# Transcurrent.net
KiCad netlist of a schematic drawn in Altium Designer
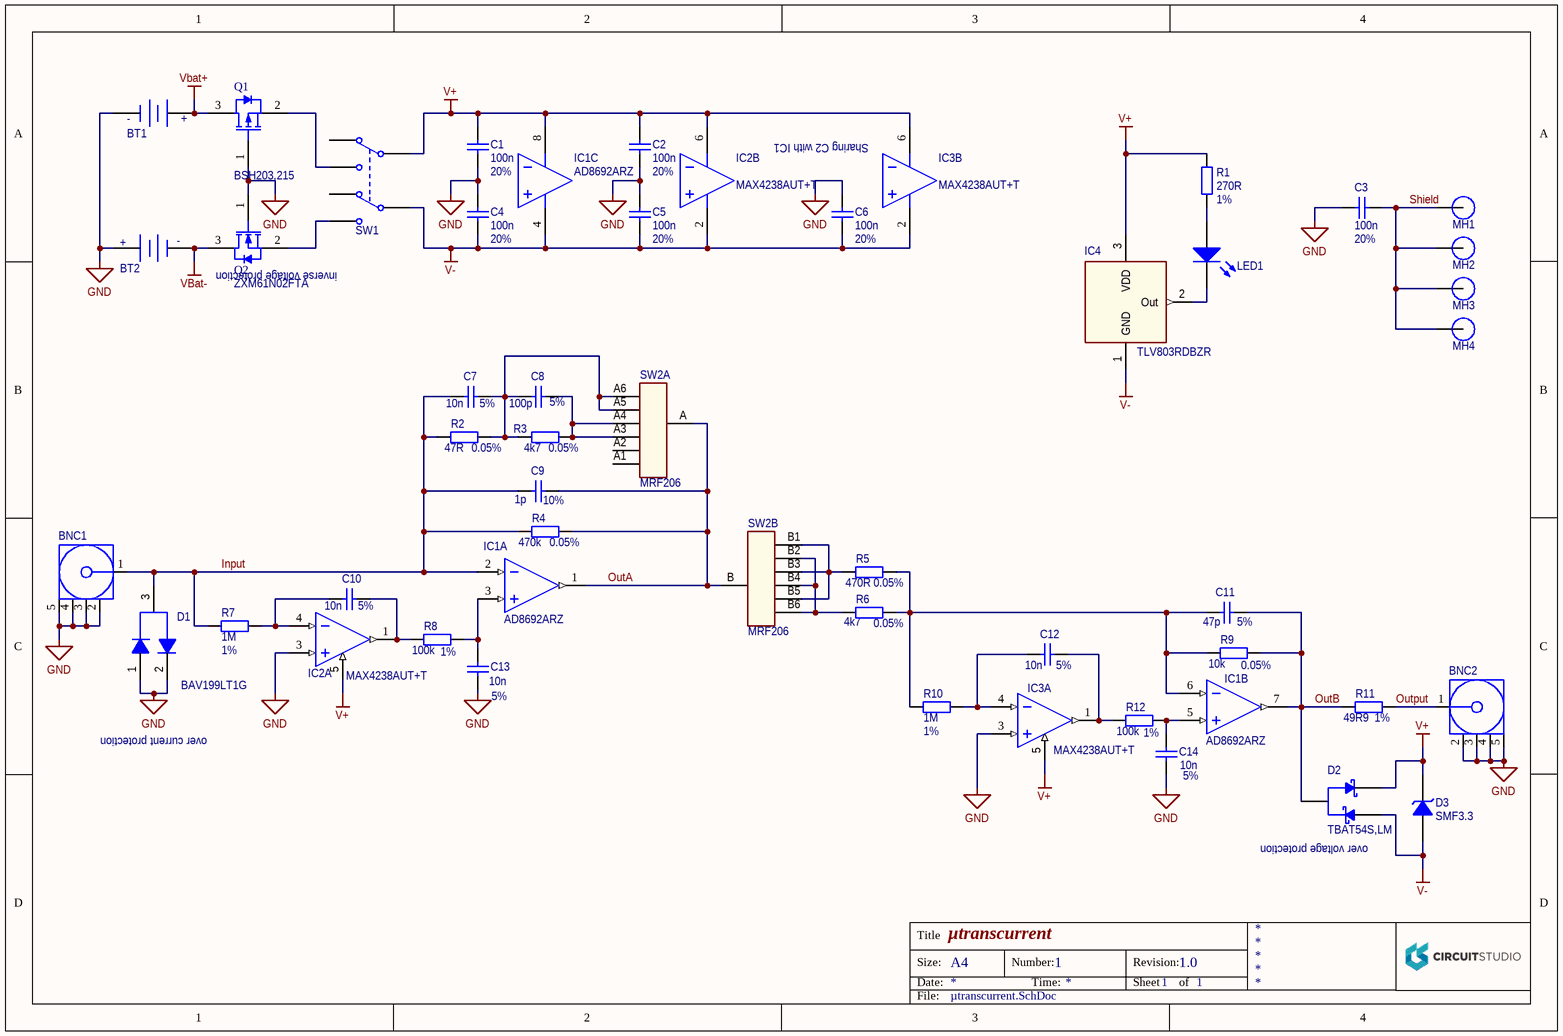
[diagram p0: Transcurrent.SchDoc]

(export (version "E")
  (design (tool "Eeschema 10.0.6"))
  (components
    (comp (ref "BNC1")
      (value "BNC female angled")
      (footprint "BNC 90°")
      (description "Connector, BNC THT 50R angled")
      (fields (field (name "MPN") "J01001A1948") (field (name "MANUFACTURER") "Telegärtner"))
      (libsource (lib "Transcurrent") (part "J01001A1948"))
    )
    (comp (ref "BNC2")
      (value "BNC female angled")
      (footprint "BNC 90°")
      (description "Connector, BNC THT 50R angled")
      (fields (field (name "MPN") "J01001A1948") (field (name "MANUFACTURER") "Telegärtner"))
      (libsource (lib "Transcurrent") (part "J01001A1948"))
    )
    (comp (ref "BT1")
      (value "Battery")
      (footprint "Keystone1020")
      (description "BATTERY HOLDER AAA SMD TAB")
      (fields (field (name "MANUFACTURER") "Keystone Electronics") (field (name "MPN") "1020"))
      (libsource (lib "Transcurrent") (part "Keystone1020"))
    )
    (comp (ref "BT2")
      (value "Battery")
      (footprint "Keystone1020")
      (description "BATTERY HOLDER AAA SMD TAB")
      (fields (field (name "MANUFACTURER") "Keystone Electronics") (field (name "MPN") "1020"))
      (libsource (lib "Transcurrent") (part "Keystone1020"))
    )
    (comp (ref "C1")
      (value "100n")
      (footprint "C0805")
      (description "Capacitor 100n 20% 0805")
      (fields
        (field (name "MANUFACTURER") "Any")
        (field (name "TOLERANCE") "20%")
        (field (name "Comment") "Cap 100n 0805")
      )
      (libsource (lib "RCL") (part "C0805_100n"))
    )
    (comp (ref "C2")
      (value "100n")
      (footprint "C0805")
      (description "Capacitor 100n 20% 0805")
      (fields
        (field (name "MANUFACTURER") "Any")
        (field (name "TOLERANCE") "20%")
        (field (name "Comment") "Cap 100n 0805")
      )
      (libsource (lib "RCL") (part "C0805_100n"))
    )
    (comp (ref "C3")
      (value "100n")
      (footprint "C0805")
      (description "Capacitor 100n 20% 0805")
      (fields
        (field (name "MANUFACTURER") "Any")
        (field (name "TOLERANCE") "20%")
        (field (name "Comment") "Cap 100n 0805")
      )
      (libsource (lib "RCL") (part "C0805_100n"))
    )
    (comp (ref "C4")
      (value "100n")
      (footprint "C0805")
      (description "Capacitor 100n 20% 0805")
      (fields
        (field (name "MANUFACTURER") "Any")
        (field (name "TOLERANCE") "20%")
        (field (name "Comment") "Cap 100n 0805")
      )
      (libsource (lib "RCL") (part "C0805_100n"))
    )
    (comp (ref "C5")
      (value "100n")
      (footprint "C0805")
      (description "Capacitor 100n 20% 0805")
      (fields
        (field (name "MANUFACTURER") "Any")
        (field (name "TOLERANCE") "20%")
        (field (name "Comment") "Cap 100n 0805")
      )
      (libsource (lib "RCL") (part "C0805_100n"))
    )
    (comp (ref "C6")
      (value "100n")
      (footprint "C0805")
      (description "Capacitor 100n 20% 0805")
      (fields
        (field (name "MANUFACTURER") "Any")
        (field (name "TOLERANCE") "20%")
        (field (name "Comment") "Cap 100n 0805")
      )
      (libsource (lib "RCL") (part "C0805_100n"))
    )
    (comp (ref "C7")
      (value "10n")
      (footprint "C0805")
      (description "CAP CER 10nF 50V C0G/NP0 0805")
      (fields
        (field (name "MPN") "C0805C103J5GACTU")
        (field (name "MANUFACTURER") "Kemet")
        (field (name "TOLERANCE") "5%")
      )
      (libsource (lib "Transcurrent") (part "C0805C103J5GACTU"))
    )
    (comp (ref "C8")
      (value "100p")
      (footprint "C0805")
      (description "CAP CER 100PF 100V C0G/NP0 0805")
      (fields
        (field (name "MPN") "CL21C101JC61PNC")
        (field (name "MANUFACTURER") "Samsung")
        (field (name "TOLERANCE") "5%")
      )
      (libsource (lib "Transcurrent") (part "CL21C101JC61PNC"))
    )
    (comp (ref "C9")
      (value "1p")
      (footprint "C0805")
      (description "CAP CER 1PF 50V NPO 0805")
      (fields
        (field (name "MPN") "CC0805BRNPO9BN1R0")
        (field (name "MANUFACTURER") "Yageo")
        (field (name "TOLERANCE") "10%")
      )
      (libsource (lib "Transcurrent") (part "CC0805BRNPO9BN1R0"))
    )
    (comp (ref "C10")
      (value "10n")
      (footprint "C0805")
      (description "CAP CER 10nF 50V C0G/NP0 0805")
      (fields
        (field (name "MPN") "C0805C103J5GACTU")
        (field (name "MANUFACTURER") "Kemet")
        (field (name "TOLERANCE") "5%")
      )
      (libsource (lib "Transcurrent") (part "C0805C103J5GACTU"))
    )
    (comp (ref "C11")
      (value "47p")
      (footprint "C0805")
      (description "CAP CER 47PF 50V C0G/NPO 0805")
      (fields
        (field (name "MPN") "CC0805JRNPO9BN470")
        (field (name "MANUFACTURER") "Yageo")
        (field (name "TOLERANCE") "5%")
      )
      (libsource (lib "Transcurrent") (part "CC0805JRNPO9BN470"))
    )
    (comp (ref "C12")
      (value "10n")
      (footprint "C0805")
      (description "CAP CER 10nF 50V C0G/NP0 0805")
      (fields
        (field (name "MPN") "C0805C103J5GACTU")
        (field (name "MANUFACTURER") "Kemet")
        (field (name "TOLERANCE") "5%")
      )
      (libsource (lib "Transcurrent") (part "C0805C103J5GACTU"))
    )
    (comp (ref "C13")
      (value "10n")
      (footprint "C0805")
      (description "CAP CER 10nF 50V C0G/NP0 0805")
      (fields
        (field (name "MPN") "C0805C103J5GACTU")
        (field (name "MANUFACTURER") "Kemet")
        (field (name "TOLERANCE") "5%")
      )
      (libsource (lib "Transcurrent") (part "C0805C103J5GACTU"))
    )
    (comp (ref "C14")
      (value "10n")
      (footprint "C0805")
      (description "CAP CER 10nF 50V C0G/NP0 0805")
      (fields
        (field (name "MPN") "C0805C103J5GACTU")
        (field (name "MANUFACTURER") "Kemet")
        (field (name "TOLERANCE") "5%")
      )
      (libsource (lib "Transcurrent") (part "C0805C103J5GACTU"))
    )
    (comp (ref "D1")
      (value "BAV199LT1G")
      (footprint "SOT23-3")
      (description "DIODE ARRAY GP 70V 215MA SOT23-3")
      (fields (field (name "MANUFACTURER") "ON Semiconductor") (field (name "MPN") "BAV199LT1G"))
      (libsource (lib "Transcurrent") (part "BAV199LT1G"))
    )
    (comp (ref "D2")
      (value "TBAT54S")
      (footprint "SOT23-3")
      (description "DIODE SCHOTTKY 30V 140MA SOT23")
      (fields (field (name "MANUFACTURER") "Toshiba") (field (name "MPN") "TBAT54S,LM"))
      (libsource (lib "Transcurrent") (part "TBAT54S"))
    )
    (comp (ref "D3")
      (value "D Zener")
      (footprint "SOD 123-FL")
      (description "TVS DIODE 3.3V 6.8V SOD123FL")
      (fields (field (name "MANUFACTURER") "Littelfuse Inc.") (field (name "MPN") "SMF3.3"))
      (libsource (lib "Transcurrent") (part "SMF3.3"))
    )
    (comp (ref "IC1")
      (value "AD8692ARZ")
      (footprint "SO8_N")
      (description "IC OPAMP GP 10MHZ RRO 8SOIC")
      (fields (field (name "MANUFACTURER") "Analog Devices") (field (name "MPN") "AD8692ARZ"))
      (libsource (lib "Transcurrent") (part "AD8692ARZ"))
    )
    (comp (ref "IC2")
      (value "MAX4238AUT+T")
      (footprint "SOT23-6")
      (description "OpAmp, low noise, auto zero")
      (fields (field (name "MANUFACTURER") "Maxim Integrated") (field (name "MPN") "MAX4238AUT+T"))
      (libsource (lib "Transcurrent") (part "MAX4238AUT+T"))
    )
    (comp (ref "IC3")
      (value "MAX4238AUT+T")
      (footprint "SOT23-6")
      (description "OpAmp, low noise, auto zero")
      (fields (field (name "MANUFACTURER") "Maxim Integrated") (field (name "MPN") "MAX4238AUT+T"))
      (libsource (lib "Transcurrent") (part "MAX4238AUT+T"))
    )
    (comp (ref "IC4")
      (value "TLV803RDBZR")
      (footprint "SOT23-3")
      (description "IC VOLT SUPERVISOR 2.64V SOT23-3")
      (fields (field (name "MANUFACTURER") "Texas Instruments") (field (name "MPN") "TLV803RDBZR"))
      (libsource (lib "Transcurrent") (part "TLV803RDBZR"))
    )
    (comp (ref "LED1")
      (value "LED")
      (footprint "LED_1206_revers")
      (description "LED rot 1206 revers")
      (fields (field (name "MPN") "156120RS75300") (field (name "MANUFACTURER") "Würth Elektronik"))
      (libsource (lib "Transcurrent") (part "156120RS75300"))
    )
    (comp (ref "MH1")
      (value "Mounting Hole M3.5")
      (footprint "M3.5 DIN84")
      (libsource (lib "Transcurrent") (part "Mounting Hole M3.5"))
    )
    (comp (ref "MH2")
      (value "Mounting Hole M3.5")
      (footprint "M3.5 DIN84")
      (libsource (lib "Transcurrent") (part "Mounting Hole M3.5"))
    )
    (comp (ref "MH3")
      (value "Mounting Hole M3.5")
      (footprint "M3.5 DIN84")
      (libsource (lib "Transcurrent") (part "Mounting Hole M3.5"))
    )
    (comp (ref "MH4")
      (value "Mounting Hole M3.5")
      (footprint "M3.5 DIN84")
      (libsource (lib "Transcurrent") (part "Mounting Hole M3.5"))
    )
    (comp (ref "Q1")
      (value "BSH203,215")
      (footprint "SOT23-3")
      (description "MOSFET P-CH 30V 470MA SOT23")
      (fields (field (name "MANUFACTURER") "Nexperia") (field (name "MPN") "BSH203,215"))
      (libsource (lib "Transcurrent") (part "BSH203,215"))
    )
    (comp (ref "Q2")
      (value "ZXM61N02FTA")
      (footprint "SOT23-3")
      (description "MOSFET N-CH 20V 1.7A SOT23-3")
      (fields (field (name "MANUFACTURER") "Diodes Inc.") (field (name "MPN") "ZXM61N02FTA"))
      (libsource (lib "Transcurrent") (part "ZXM61N02FTA"))
    )
    (comp (ref "R1")
      (value "270R")
      (footprint "R0805")
      (description "Resistor 270R 1% 0805")
      (fields
        (field (name "MANUFACTURER") "Any")
        (field (name "TOLERANCE") "1%")
        (field (name "Comment") "Res 270R 0805")
      )
      (libsource (lib "RCL") (part "R0805_270R"))
    )
    (comp (ref "R2")
      (value "47R")
      (footprint "R0805")
      (description "RES SMD 47 OHM 0.05% 1/8W 0805")
      (fields
        (field (name "MPN") "RG2012N-470-W-T1")
        (field (name "MANUFACTURER") "Susumu")
        (field (name "TOLERANCE") "0.05%")
      )
      (libsource (lib "Transcurrent") (part "RG2012N-470-W-T1"))
    )
    (comp (ref "R3")
      (value "4k7")
      (footprint "R0805")
      (description "RES SMD 4k7 OHM 0.05% 1/8W 0805")
      (fields
        (field (name "MPN") "ERA-6ARW472V")
        (field (name "MANUFACTURER") "Panasonic")
        (field (name "TOLERANCE") "0.05%")
      )
      (libsource (lib "Transcurrent") (part "ERA-6ARW472V"))
    )
    (comp (ref "R4")
      (value "470k")
      (footprint "R0805")
      (description "RES SMD 470K OHM 0.05% 1/8W 0805")
      (fields
        (field (name "MPN") "RG2012N-474-W-T1")
        (field (name "MANUFACTURER") "Susumu")
        (field (name "TOLERANCE") "0.05%")
      )
      (libsource (lib "Transcurrent") (part "RG2012N-474-W-T1"))
    )
    (comp (ref "R5")
      (value "470R")
      (footprint "R0805")
      (description "RES SMD 470 OHM 0.05% 1/8W 0805")
      (fields
        (field (name "MPN") "RG2012N-471-W-T1")
        (field (name "MANUFACTURER") "Susumu")
        (field (name "TOLERANCE") "0.05%")
      )
      (libsource (lib "Transcurrent") (part "RG2012N-471-W-T1"))
    )
    (comp (ref "R6")
      (value "4k7")
      (footprint "R0805")
      (description "RES SMD 4k7 OHM 0.05% 1/8W 0805")
      (fields
        (field (name "MPN") "ERA-6ARW472V")
        (field (name "MANUFACTURER") "Panasonic")
        (field (name "TOLERANCE") "0.05%")
      )
      (libsource (lib "Transcurrent") (part "ERA-6ARW472V"))
    )
    (comp (ref "R7")
      (value "1M")
      (footprint "R0805")
      (description "Resistor 1M 1% 0805")
      (fields
        (field (name "TOLERANCE") "1%")
        (field (name "MANUFACTURER") "Any")
        (field (name "Comment") "Res 1M 0805")
      )
      (libsource (lib "RCL") (part "R0805_1M"))
    )
    (comp (ref "R8")
      (value "100k")
      (footprint "R0805")
      (description "Resistor 100k 1% 0805")
      (fields
        (field (name "TOLERANCE") "1%")
        (field (name "MANUFACTURER") "Any")
        (field (name "Comment") "Res 100k 0805")
      )
      (libsource (lib "RCL") (part "R0805_100k"))
    )
    (comp (ref "R9")
      (value "10k")
      (footprint "R0805")
      (description "RES SMD 10K OHM 0.05% 1/8W 0805")
      (fields
        (field (name "MPN") "RG2012N-103-W-T1")
        (field (name "MANUFACTURER") "Susumu")
        (field (name "TOLERANCE") "0.05%")
      )
      (libsource (lib "Transcurrent") (part "RG2012N-103-W-T1"))
    )
    (comp (ref "R10")
      (value "1M")
      (footprint "R0805")
      (description "Resistor 1M 1% 0805")
      (fields
        (field (name "TOLERANCE") "1%")
        (field (name "MANUFACTURER") "Any")
        (field (name "Comment") "Res 1M 0805")
      )
      (libsource (lib "RCL") (part "R0805_1M"))
    )
    (comp (ref "R11")
      (value "49R9")
      (footprint "R0805")
      (description "Resistor 49R9 1% 0805")
      (fields
        (field (name "MANUFACTURER") "Any")
        (field (name "TOLERANCE") "1%")
        (field (name "Comment") "Res 49R9 0805")
      )
      (libsource (lib "MyLibrary") (part "R0805_49R9"))
    )
    (comp (ref "R12")
      (value "100k")
      (footprint "R0805")
      (description "Resistor 100k 1% 0805")
      (fields
        (field (name "TOLERANCE") "1%")
        (field (name "MANUFACTURER") "Any")
        (field (name "Comment") "Res 100k 0805")
      )
      (libsource (lib "RCL") (part "R0805_100k"))
    )
    (comp (ref "SW1")
      (value "MMP 221")
      (footprint "MMP 221")
      (description "Switch, DPDT THT mini")
      (fields (field (name "MANUFACTURER") "Knitterswitch") (field (name "MPN") "221"))
      (libsource (lib "Transcurrent") (part "MMP 221"))
    )
    (comp (ref "SW2")
      (value "MRF206")
      (footprint "MKF206")
      (description "DP6T Rotary Switch")
      (fields (field (name "MANUFACTURER") "NKK Switches"))
      (libsource (lib "") (part "MRF206_1"))
    )
  )
  (nets
    (net (code "1") (name "/Input") (class "Default")
      (node (ref "BNC1") (pin "1") (pinfunction "Signal_1") (pintype "passive"))
      (node (ref "C7") (pin "1") (pinfunction "1_1") (pintype "passive"))
      (node (ref "C9") (pin "1") (pinfunction "1_1") (pintype "passive"))
      (node (ref "D1") (pin "3") (pinfunction "3_3") (pintype "passive"))
      (node (ref "IC1") (pin "2") (pinfunction "INA-_2") (pintype "input"))
      (node (ref "R2") (pin "1") (pinfunction "1_1") (pintype "passive"))
      (node (ref "R4") (pin "1") (pinfunction "1_1") (pintype "passive"))
      (node (ref "R7") (pin "1") (pinfunction "1_1") (pintype "passive"))
    )
    (net (code "2") (name "/OutA") (class "Default")
      (node (ref "C9") (pin "2") (pinfunction "2_2") (pintype "passive"))
      (node (ref "IC1") (pin "1") (pinfunction "OUTA_1") (pintype "output"))
      (node (ref "R4") (pin "2") (pinfunction "2_2") (pintype "passive"))
      (node (ref "SW2") (pin "A") (pinfunction "A_A") (pintype "passive"))
      (node (ref "SW2") (pin "B") (pinfunction "B_B") (pintype "passive"))
    )
    (net (code "3") (name "/OutB") (class "Default")
      (node (ref "C11") (pin "2") (pinfunction "2_2") (pintype "passive"))
      (node (ref "D2") (pin "3") (pinfunction "3_3") (pintype "passive"))
      (node (ref "IC1") (pin "7") (pinfunction "OUTB_7") (pintype "output"))
      (node (ref "R11") (pin "1") (pinfunction "1_1") (pintype "passive"))
      (node (ref "R9") (pin "2") (pinfunction "2_2") (pintype "passive"))
    )
    (net (code "4") (name "/Output") (class "Default")
      (node (ref "BNC2") (pin "1") (pinfunction "Signal_1") (pintype "passive"))
      (node (ref "R11") (pin "2") (pinfunction "2_2") (pintype "passive"))
    )
    (net (code "5") (name "/Shield") (class "Default")
      (node (ref "C3") (pin "2") (pinfunction "2_2") (pintype "passive"))
      (node (ref "MH1") (pin "0") (pinfunction "0_0") (pintype "passive"))
      (node (ref "MH2") (pin "0") (pinfunction "0_0") (pintype "passive"))
      (node (ref "MH3") (pin "0") (pinfunction "0_0") (pintype "passive"))
      (node (ref "MH4") (pin "0") (pinfunction "0_0") (pintype "passive"))
    )
    (net (code "6") (name "GND") (class "Default")
      (node (ref "BNC1") (pin "2") (pinfunction "GND_2") (pintype "power_in"))
      (node (ref "BNC1") (pin "3") (pinfunction "GND_3") (pintype "power_in"))
      (node (ref "BNC1") (pin "4") (pinfunction "GND_4") (pintype "power_in"))
      (node (ref "BNC1") (pin "5") (pinfunction "GND_5") (pintype "power_in"))
      (node (ref "BNC2") (pin "2") (pinfunction "GND_2") (pintype "power_in"))
      (node (ref "BNC2") (pin "3") (pinfunction "GND_3") (pintype "power_in"))
      (node (ref "BNC2") (pin "4") (pinfunction "GND_4") (pintype "power_in"))
      (node (ref "BNC2") (pin "5") (pinfunction "GND_5") (pintype "power_in"))
      (node (ref "BT1") (pin "1") (pinfunction "-_1") (pintype "passive"))
      (node (ref "BT2") (pin "2") (pinfunction "+_2") (pintype "power_in"))
      (node (ref "C1") (pin "1") (pinfunction "1_1") (pintype "passive"))
      (node (ref "C13") (pin "1") (pinfunction "1_1") (pintype "passive"))
      (node (ref "C14") (pin "1") (pinfunction "1_1") (pintype "passive"))
      (node (ref "C2") (pin "1") (pinfunction "1_1") (pintype "passive"))
      (node (ref "C3") (pin "1") (pinfunction "1_1") (pintype "passive"))
      (node (ref "C4") (pin "2") (pinfunction "2_2") (pintype "passive"))
      (node (ref "C5") (pin "2") (pinfunction "2_2") (pintype "passive"))
      (node (ref "C6") (pin "2") (pinfunction "2_2") (pintype "passive"))
      (node (ref "D1") (pin "1") (pinfunction "1_1") (pintype "passive"))
      (node (ref "D1") (pin "2") (pinfunction "2_2") (pintype "passive"))
      (node (ref "IC2") (pin "3") (pinfunction "IN+_3") (pintype "input"))
      (node (ref "IC3") (pin "3") (pinfunction "IN+_3") (pintype "input"))
      (node (ref "Q1") (pin "1") (pinfunction "G_1") (pintype "passive"))
      (node (ref "Q2") (pin "1") (pinfunction "G_1") (pintype "passive"))
    )
    (net (code "7") (name "Net-(C7-Pad2)") (class "Default")
      (node (ref "C7") (pin "2") (pinfunction "2_2") (pintype "passive"))
      (node (ref "C8") (pin "1") (pinfunction "1_1") (pintype "passive"))
      (node (ref "R2") (pin "2") (pinfunction "2_2") (pintype "passive"))
      (node (ref "R3") (pin "1") (pinfunction "1_1") (pintype "passive"))
      (node (ref "SW2") (pin "A5") (pinfunction "A5_A5") (pintype "passive"))
      (node (ref "SW2") (pin "A6") (pinfunction "A6_A6") (pintype "passive"))
    )
    (net (code "8") (name "Net-(C8-Pad2)") (class "Default")
      (node (ref "C8") (pin "2") (pinfunction "2_2") (pintype "passive"))
      (node (ref "R3") (pin "2") (pinfunction "2_2") (pintype "passive"))
      (node (ref "SW2") (pin "A3") (pinfunction "A3_A3") (pintype "passive"))
      (node (ref "SW2") (pin "A4") (pinfunction "A4_A4") (pintype "passive"))
    )
    (net (code "9") (name "Net-(IC1A-INA+)") (class "Default")
      (node (ref "C13") (pin "2") (pinfunction "2_2") (pintype "passive"))
      (node (ref "IC1") (pin "3") (pinfunction "INA+_3") (pintype "input"))
      (node (ref "R8") (pin "2") (pinfunction "2_2") (pintype "passive"))
    )
    (net (code "10") (name "Net-(IC1B-INB+)") (class "Default")
      (node (ref "C14") (pin "2") (pinfunction "2_2") (pintype "passive"))
      (node (ref "IC1") (pin "5") (pinfunction "INB+_5") (pintype "input"))
      (node (ref "R12") (pin "2") (pinfunction "2_2") (pintype "passive"))
    )
    (net (code "11") (name "Net-(IC1B-INB-)") (class "Default")
      (node (ref "C11") (pin "1") (pinfunction "1_1") (pintype "passive"))
      (node (ref "IC1") (pin "6") (pinfunction "INB-_6") (pintype "input"))
      (node (ref "R10") (pin "1") (pinfunction "1_1") (pintype "passive"))
      (node (ref "R5") (pin "2") (pinfunction "2_2") (pintype "passive"))
      (node (ref "R6") (pin "2") (pinfunction "2_2") (pintype "passive"))
      (node (ref "R9") (pin "1") (pinfunction "1_1") (pintype "passive"))
    )
    (net (code "12") (name "Net-(IC2A-IN-)") (class "Default")
      (node (ref "C10") (pin "1") (pinfunction "1_1") (pintype "passive"))
      (node (ref "IC2") (pin "4") (pinfunction "IN-_4") (pintype "input"))
      (node (ref "R7") (pin "2") (pinfunction "2_2") (pintype "passive"))
    )
    (net (code "13") (name "Net-(IC2A-OUT)") (class "Default")
      (node (ref "C10") (pin "2") (pinfunction "2_2") (pintype "passive"))
      (node (ref "IC2") (pin "1") (pinfunction "OUT_1") (pintype "output"))
      (node (ref "R8") (pin "1") (pinfunction "1_1") (pintype "passive"))
    )
    (net (code "14") (name "Net-(IC3A-IN-)") (class "Default")
      (node (ref "C12") (pin "1") (pinfunction "1_1") (pintype "passive"))
      (node (ref "IC3") (pin "4") (pinfunction "IN-_4") (pintype "input"))
      (node (ref "R10") (pin "2") (pinfunction "2_2") (pintype "passive"))
    )
    (net (code "15") (name "Net-(IC3A-OUT)") (class "Default")
      (node (ref "C12") (pin "2") (pinfunction "2_2") (pintype "passive"))
      (node (ref "IC3") (pin "1") (pinfunction "OUT_1") (pintype "output"))
      (node (ref "R12") (pin "1") (pinfunction "1_1") (pintype "passive"))
    )
    (net (code "16") (name "Net-(IC4-Out)") (class "Default")
      (node (ref "IC4") (pin "2") (pinfunction "Out_2") (pintype "output"))
      (node (ref "LED1") (pin "2") (pinfunction "K_2") (pintype "passive"))
    )
    (net (code "17") (name "Net-(LED1-A)") (class "Default")
      (node (ref "LED1") (pin "1") (pinfunction "A_1") (pintype "passive"))
      (node (ref "R1") (pin "1") (pinfunction "1_1") (pintype "passive"))
    )
    (net (code "18") (name "Net-(Q1-S)") (class "Default")
      (node (ref "Q1") (pin "2") (pinfunction "S_2") (pintype "passive"))
      (node (ref "SW1") (pin "3") (pinfunction "NO1_3") (pintype "passive"))
    )
    (net (code "19") (name "Net-(Q2-S)") (class "Default")
      (node (ref "Q2") (pin "2") (pinfunction "S_2") (pintype "passive"))
      (node (ref "SW1") (pin "6") (pinfunction "NO2_6") (pintype "passive"))
    )
    (net (code "20") (name "Net-(R5-Pad1)") (class "Default")
      (node (ref "R5") (pin "1") (pinfunction "1_1") (pintype "passive"))
      (node (ref "SW2") (pin "B1") (pinfunction "B1_B1") (pintype "passive"))
      (node (ref "SW2") (pin "B3") (pinfunction "B3_B3") (pintype "passive"))
      (node (ref "SW2") (pin "B5") (pinfunction "B5_B5") (pintype "passive"))
    )
    (net (code "21") (name "Net-(R6-Pad1)") (class "Default")
      (node (ref "R6") (pin "1") (pinfunction "1_1") (pintype "passive"))
      (node (ref "SW2") (pin "B2") (pinfunction "B2_B2") (pintype "passive"))
      (node (ref "SW2") (pin "B4") (pinfunction "B4_B4") (pintype "passive"))
      (node (ref "SW2") (pin "B6") (pinfunction "B6_B6") (pintype "passive"))
    )
    (net (code "22") (name "V+") (class "Default")
      (node (ref "C1") (pin "2") (pinfunction "2_2") (pintype "passive"))
      (node (ref "C2") (pin "2") (pinfunction "2_2") (pintype "passive"))
      (node (ref "D2") (pin "2") (pinfunction "2_2") (pintype "passive"))
      (node (ref "D3") (pin "2") (pinfunction "K_2") (pintype "passive"))
      (node (ref "IC1") (pin "8") (pinfunction "V+_8") (pintype "power_in"))
      (node (ref "IC2") (pin "5") (pinfunction "~{SHDN}_5") (pintype "input"))
      (node (ref "IC2") (pin "6") (pinfunction "V+_6") (pintype "power_in"))
      (node (ref "IC3") (pin "5") (pinfunction "~{SHDN}_5") (pintype "input"))
      (node (ref "IC3") (pin "6") (pinfunction "V+_6") (pintype "power_in"))
      (node (ref "IC4") (pin "3") (pinfunction "VDD_3") (pintype "power_in"))
      (node (ref "R1") (pin "2") (pinfunction "2_2") (pintype "passive"))
      (node (ref "SW1") (pin "2") (pinfunction "COMMON1_2") (pintype "passive"))
    )
    (net (code "23") (name "V-") (class "Default")
      (node (ref "C4") (pin "1") (pinfunction "1_1") (pintype "passive"))
      (node (ref "C5") (pin "1") (pinfunction "1_1") (pintype "passive"))
      (node (ref "C6") (pin "1") (pinfunction "1_1") (pintype "passive"))
      (node (ref "D2") (pin "1") (pinfunction "1_1") (pintype "passive"))
      (node (ref "D3") (pin "1") (pinfunction "A_1") (pintype "passive"))
      (node (ref "IC1") (pin "4") (pinfunction "V-_4") (pintype "power_in"))
      (node (ref "IC2") (pin "2") (pinfunction "V-_2") (pintype "power_in"))
      (node (ref "IC3") (pin "2") (pinfunction "V-_2") (pintype "power_in"))
      (node (ref "IC4") (pin "1") (pinfunction "GND_1") (pintype "power_in"))
      (node (ref "SW1") (pin "5") (pinfunction "COMMON2_5") (pintype "passive"))
    )
    (net (code "24") (name "VBat-") (class "Default")
      (node (ref "BT2") (pin "1") (pinfunction "-_1") (pintype "passive"))
      (node (ref "Q2") (pin "3") (pinfunction "D_3") (pintype "passive"))
    )
    (net (code "25") (name "Vbat+") (class "Default")
      (node (ref "BT1") (pin "2") (pinfunction "+_2") (pintype "power_in"))
      (node (ref "Q1") (pin "3") (pinfunction "D_3") (pintype "passive"))
    )
    (net (code "26") (name "unconnected-(SW1-NC1-Pad1)") (class "Default")
      (node (ref "SW1") (pin "1") (pinfunction "NC1_1") (pintype "passive"))
    )
    (net (code "27") (name "unconnected-(SW1-NC2-Pad4)") (class "Default")
      (node (ref "SW1") (pin "4") (pinfunction "NC2_4") (pintype "passive"))
    )
    (net (code "28") (name "unconnected-(SW2-PadA1)") (class "Default")
      (node (ref "SW2") (pin "A1") (pinfunction "A1_A1") (pintype "passive"))
    )
    (net (code "29") (name "unconnected-(SW2-PadA2)") (class "Default")
      (node (ref "SW2") (pin "A2") (pinfunction "A2_A2") (pintype "passive"))
    )
  )
)
